# Absolute_value_circuit.net
KiCad netlist of a schematic drawn in EAGLE
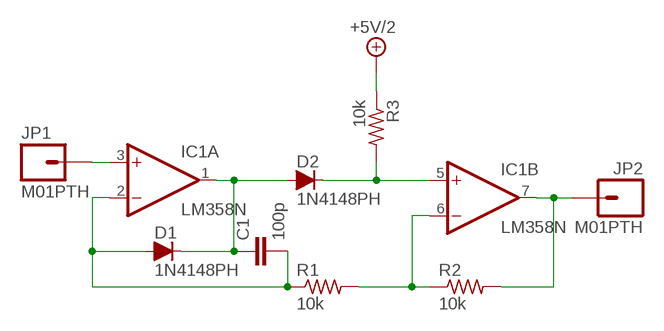
[diagram p0: schematic, sheet 1]

(export (version "E")
  (design (tool "Eeschema 10.0.6"))
  (components
    (comp (ref "C1")
      (value "100p")
      (footprint "eagle-import:C025-025X050")
      (libsource (lib "eagle-import") (part "C-EU025-025X050"))
    )
    (comp (ref "D1")
      (value "1N4148PH")
      (footprint "eagle-import:DO35-7")
      (libsource (lib "eagle-import") (part "1N4148PH"))
    )
    (comp (ref "D2")
      (value "1N4148PH")
      (footprint "eagle-import:DO35-7")
      (libsource (lib "eagle-import") (part "1N4148PH"))
    )
    (comp (ref "IC1")
      (value "LM358N")
      (footprint "eagle-import:DIL08")
      (libsource (lib "eagle-import") (part "LM358N"))
    )
    (comp (ref "JP1")
      (value "M01PTH")
      (footprint "eagle-import:1X01")
      (libsource (lib "eagle-import") (part "M01PTH"))
    )
    (comp (ref "JP2")
      (value "M01PTH")
      (footprint "eagle-import:1X01")
      (libsource (lib "eagle-import") (part "M01PTH"))
    )
    (comp (ref "R1")
      (value "10k")
      (footprint "eagle-import:0204_5")
      (libsource (lib "eagle-import") (part "R-US_0204/5"))
    )
    (comp (ref "R2")
      (value "10k")
      (footprint "eagle-import:0204_5")
      (libsource (lib "eagle-import") (part "R-US_0204/5"))
    )
    (comp (ref "R3")
      (value "10k")
      (footprint "eagle-import:0204_5")
      (libsource (lib "eagle-import") (part "R-US_0204/5"))
    )
  )
  (nets
    (net (code "1") (name "+5V{slash}2") (class "Default")
      (node (ref "R3") (pin "1") (pinfunction "1_1") (pintype "passive"))
    )
    (net (code "2") (name "Net-(IC1A-+IN)") (class "Default")
      (node (ref "IC1") (pin "3") (pinfunction "+IN_3") (pintype "input"))
      (node (ref "JP1") (pin "1") (pinfunction "1_1") (pintype "passive"))
    )
    (net (code "3") (name "Net-(IC1A--IN)") (class "Default")
      (node (ref "C1") (pin "2") (pinfunction "2_2") (pintype "passive"))
      (node (ref "D1") (pin "A") (pinfunction "A_A") (pintype "passive"))
      (node (ref "IC1") (pin "2") (pinfunction "-IN_2") (pintype "input"))
      (node (ref "R1") (pin "1") (pinfunction "1_1") (pintype "passive"))
    )
    (net (code "4") (name "Net-(IC1A-OUT)") (class "Default")
      (node (ref "C1") (pin "1") (pinfunction "1_1") (pintype "passive"))
      (node (ref "D1") (pin "C") (pinfunction "C_C") (pintype "passive"))
      (node (ref "D2") (pin "A") (pinfunction "A_A") (pintype "passive"))
      (node (ref "IC1") (pin "1") (pinfunction "OUT_1") (pintype "output"))
    )
    (net (code "5") (name "Net-(IC1B-+IN)") (class "Default")
      (node (ref "D2") (pin "C") (pinfunction "C_C") (pintype "passive"))
      (node (ref "IC1") (pin "5") (pinfunction "+IN_5") (pintype "input"))
      (node (ref "R3") (pin "2") (pinfunction "2_2") (pintype "passive"))
    )
    (net (code "6") (name "Net-(IC1B--IN)") (class "Default")
      (node (ref "IC1") (pin "6") (pinfunction "-IN_6") (pintype "input"))
      (node (ref "R1") (pin "2") (pinfunction "2_2") (pintype "passive"))
      (node (ref "R2") (pin "1") (pinfunction "1_1") (pintype "passive"))
    )
    (net (code "7") (name "Net-(IC1B-OUT)") (class "Default")
      (node (ref "IC1") (pin "7") (pinfunction "OUT_7") (pintype "output"))
      (node (ref "JP2") (pin "1") (pinfunction "1_1") (pintype "passive"))
      (node (ref "R2") (pin "2") (pinfunction "2_2") (pintype "passive"))
    )
  )
)
